# Bluetooth_Low_Energy_Circuit.net
KiCad netlist of a schematic drawn in EAGLE
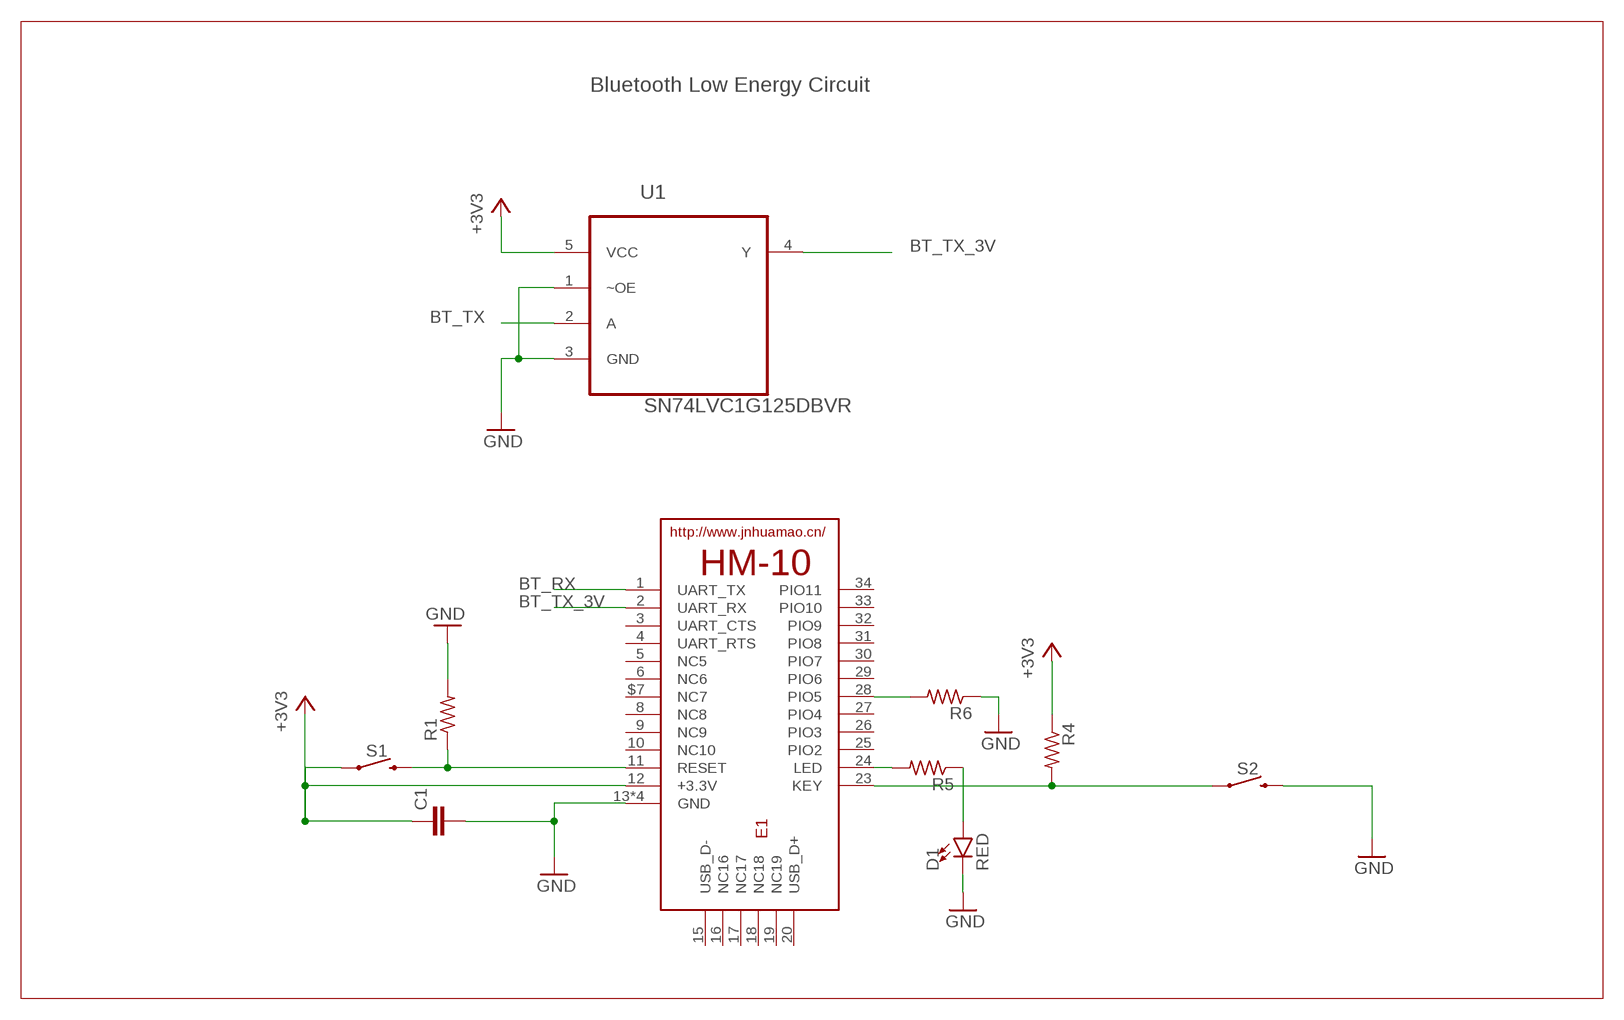
[diagram p0: schematic, sheet 1]

(export (version "E")
  (design (tool "Eeschema 10.0.6"))
  (components
    (comp (ref "C1")
      (value "C-EUC0805")
      (footprint "eagle-import:C0805")
      (libsource (lib "eagle-import") (part "C-EUC0805"))
    )
    (comp (ref "D1")
      (value "RED")
      (footprint "eagle-import:LED-0603")
      (libsource (lib "eagle-import") (part "LED-RED0603"))
    )
    (comp (ref "E1")
      (value "HM-10-BOARD")
      (footprint "eagle-import:26.9X13X2.2_BOARD")
      (libsource (lib "eagle-import") (part "HM-10-BOARD"))
    )
    (comp (ref "R1")
      (value "R-US_R0805")
      (footprint "eagle-import:R0805")
      (libsource (lib "eagle-import") (part "R-US_R0805"))
    )
    (comp (ref "R4")
      (value "R-US_R0805")
      (footprint "eagle-import:R0805")
      (libsource (lib "eagle-import") (part "R-US_R0805"))
    )
    (comp (ref "R5")
      (value "R-US_R0805")
      (footprint "eagle-import:R0805")
      (libsource (lib "eagle-import") (part "R-US_R0805"))
    )
    (comp (ref "R6")
      (value "R-US_R0805")
      (footprint "eagle-import:R0805")
      (libsource (lib "eagle-import") (part "R-US_R0805"))
    )
    (comp (ref "S1")
      (value "MOMENTARY-SWITCH-SPST-SMD-6.0X3.5MM")
      (footprint "eagle-import:TACTILE_SWITCH_SMD_6.0X3.5MM")
      (libsource (lib "eagle-import") (part "MOMENTARY-SWITCH-SPST-SMD-6.0X3.5MM"))
    )
    (comp (ref "S2")
      (value "MOMENTARY-SWITCH-SPST-SMD-6.0X3.5MM")
      (footprint "eagle-import:TACTILE_SWITCH_SMD_6.0X3.5MM")
      (libsource (lib "eagle-import") (part "MOMENTARY-SWITCH-SPST-SMD-6.0X3.5MM"))
    )
    (comp (ref "U1")
      (value "SN74LVC1G125DBVR")
      (footprint "eagle-import:SOT95P280X145-5N")
      (fields (field (name "MF") "Texas Instruments"))
      (libsource (lib "eagle-import") (part "SN74LVC1G125DBVR"))
    )
  )
  (nets
    (net (code "1") (name "+3V3") (class "Default")
      (node (ref "C1") (pin "1") (pinfunction "1_1") (pintype "passive"))
      (node (ref "E1") (pin "12") (pinfunction "+3.3V_12") (pintype "bidirectional"))
      (node (ref "R4") (pin "1") (pinfunction "1_1") (pintype "passive"))
      (node (ref "S1") (pin "1") (pinfunction "1_1") (pintype "passive"))
      (node (ref "U1") (pin "5") (pinfunction "VCC_5") (pintype "power_in"))
    )
    (net (code "2") (name "/BT_RX") (class "Default")
      (node (ref "E1") (pin "1") (pinfunction "UART_TX_1") (pintype "bidirectional"))
    )
    (net (code "3") (name "/BT_TX") (class "Default")
      (node (ref "U1") (pin "2") (pinfunction "A_2") (pintype "input"))
    )
    (net (code "4") (name "/BT_TX_3V") (class "Default")
      (node (ref "E1") (pin "2") (pinfunction "UART_RX_2") (pintype "bidirectional"))
      (node (ref "U1") (pin "4") (pinfunction "Y_4") (pintype "output"))
    )
    (net (code "5") (name "GND") (class "Default")
      (node (ref "C1") (pin "2") (pinfunction "2_2") (pintype "passive"))
      (node (ref "D1") (pin "C") (pinfunction "C_C") (pintype "passive"))
      (node (ref "E1") (pin "13") (pinfunction "GND_13") (pintype "bidirectional"))
      (node (ref "E1") (pin "14") (pinfunction "GND_14") (pintype "bidirectional"))
      (node (ref "E1") (pin "21") (pinfunction "GND_21") (pintype "bidirectional"))
      (node (ref "E1") (pin "22") (pinfunction "GND_22") (pintype "bidirectional"))
      (node (ref "R1") (pin "2") (pinfunction "2_2") (pintype "passive"))
      (node (ref "R6") (pin "1") (pinfunction "1_1") (pintype "passive"))
      (node (ref "S2") (pin "2") (pinfunction "2_2") (pintype "passive"))
      (node (ref "U1") (pin "1") (pinfunction "~{OE}_1") (pintype "input"))
      (node (ref "U1") (pin "3") (pinfunction "GND_3") (pintype "passive"))
    )
    (net (code "6") (name "Net-(D1-PadA)") (class "Default")
      (node (ref "D1") (pin "A") (pinfunction "A_A") (pintype "passive"))
      (node (ref "R5") (pin "1") (pinfunction "1_1") (pintype "passive"))
    )
    (net (code "7") (name "Net-(E1-KEY)") (class "Default")
      (node (ref "E1") (pin "23") (pinfunction "KEY_23") (pintype "bidirectional"))
      (node (ref "R4") (pin "2") (pinfunction "2_2") (pintype "passive"))
      (node (ref "S2") (pin "1") (pinfunction "1_1") (pintype "passive"))
    )
    (net (code "8") (name "Net-(E1-LED)") (class "Default")
      (node (ref "E1") (pin "24") (pinfunction "LED_24") (pintype "bidirectional"))
      (node (ref "R5") (pin "2") (pinfunction "2_2") (pintype "passive"))
    )
    (net (code "9") (name "Net-(E1-PIO5)") (class "Default")
      (node (ref "E1") (pin "28") (pinfunction "PIO5_28") (pintype "bidirectional"))
      (node (ref "R6") (pin "2") (pinfunction "2_2") (pintype "passive"))
    )
    (net (code "10") (name "Net-(E1-RESET)") (class "Default")
      (node (ref "E1") (pin "11") (pinfunction "RESET_11") (pintype "bidirectional"))
      (node (ref "R1") (pin "1") (pinfunction "1_1") (pintype "passive"))
      (node (ref "S1") (pin "2") (pinfunction "2_2") (pintype "passive"))
    )
    (net (code "11") (name "unconnected-(E1-NC5-Pad5)") (class "Default")
      (node (ref "E1") (pin "5") (pinfunction "NC5_5") (pintype "bidirectional"))
    )
    (net (code "12") (name "unconnected-(E1-NC6-Pad6)") (class "Default")
      (node (ref "E1") (pin "6") (pinfunction "NC6_6") (pintype "bidirectional"))
    )
    (net (code "13") (name "unconnected-(E1-NC7-Pad$7)") (class "Default")
      (node (ref "E1") (pin "$7") (pinfunction "NC7_$7") (pintype "bidirectional"))
    )
    (net (code "14") (name "unconnected-(E1-NC8-Pad8)") (class "Default")
      (node (ref "E1") (pin "8") (pinfunction "NC8_8") (pintype "bidirectional"))
    )
    (net (code "15") (name "unconnected-(E1-NC9-Pad9)") (class "Default")
      (node (ref "E1") (pin "9") (pinfunction "NC9_9") (pintype "bidirectional"))
    )
    (net (code "16") (name "unconnected-(E1-NC10-Pad10)") (class "Default")
      (node (ref "E1") (pin "10") (pinfunction "NC10_10") (pintype "bidirectional"))
    )
    (net (code "17") (name "unconnected-(E1-NC16-Pad16)") (class "Default")
      (node (ref "E1") (pin "16") (pinfunction "NC16_16") (pintype "bidirectional"))
    )
    (net (code "18") (name "unconnected-(E1-NC17-Pad17)") (class "Default")
      (node (ref "E1") (pin "17") (pinfunction "NC17_17") (pintype "bidirectional"))
    )
    (net (code "19") (name "unconnected-(E1-NC18-Pad18)") (class "Default")
      (node (ref "E1") (pin "18") (pinfunction "NC18_18") (pintype "bidirectional"))
    )
    (net (code "20") (name "unconnected-(E1-NC19-Pad19)") (class "Default")
      (node (ref "E1") (pin "19") (pinfunction "NC19_19") (pintype "bidirectional"))
    )
    (net (code "21") (name "unconnected-(E1-PIO2-Pad25)") (class "Default")
      (node (ref "E1") (pin "25") (pinfunction "PIO2_25") (pintype "bidirectional"))
    )
    (net (code "22") (name "unconnected-(E1-PIO3-Pad26)") (class "Default")
      (node (ref "E1") (pin "26") (pinfunction "PIO3_26") (pintype "bidirectional"))
    )
    (net (code "23") (name "unconnected-(E1-PIO4-Pad27)") (class "Default")
      (node (ref "E1") (pin "27") (pinfunction "PIO4_27") (pintype "bidirectional"))
    )
    (net (code "24") (name "unconnected-(E1-PIO6-Pad29)") (class "Default")
      (node (ref "E1") (pin "29") (pinfunction "PIO6_29") (pintype "bidirectional"))
    )
    (net (code "25") (name "unconnected-(E1-PIO7-Pad30)") (class "Default")
      (node (ref "E1") (pin "30") (pinfunction "PIO7_30") (pintype "bidirectional"))
    )
    (net (code "26") (name "unconnected-(E1-PIO8-Pad31)") (class "Default")
      (node (ref "E1") (pin "31") (pinfunction "PIO8_31") (pintype "bidirectional"))
    )
    (net (code "27") (name "unconnected-(E1-PIO9-Pad32)") (class "Default")
      (node (ref "E1") (pin "32") (pinfunction "PIO9_32") (pintype "bidirectional"))
    )
    (net (code "28") (name "unconnected-(E1-PIO10-Pad33)") (class "Default")
      (node (ref "E1") (pin "33") (pinfunction "PIO10_33") (pintype "bidirectional"))
    )
    (net (code "29") (name "unconnected-(E1-PIO11-Pad34)") (class "Default")
      (node (ref "E1") (pin "34") (pinfunction "PIO11_34") (pintype "bidirectional"))
    )
    (net (code "30") (name "unconnected-(E1-UART_CTS-Pad3)") (class "Default")
      (node (ref "E1") (pin "3") (pinfunction "UART_CTS_3") (pintype "bidirectional"))
    )
    (net (code "31") (name "unconnected-(E1-UART_RTS-Pad4)") (class "Default")
      (node (ref "E1") (pin "4") (pinfunction "UART_RTS_4") (pintype "bidirectional"))
    )
    (net (code "32") (name "unconnected-(E1-USB_D+-Pad20)") (class "Default")
      (node (ref "E1") (pin "20") (pinfunction "USB_D+_20") (pintype "bidirectional"))
    )
    (net (code "33") (name "unconnected-(E1-USB_D--Pad15)") (class "Default")
      (node (ref "E1") (pin "15") (pinfunction "USB_D-_15") (pintype "bidirectional"))
    )
  )
)
